# Connectors.net
KiCad netlist of a schematic drawn in Altium Designer
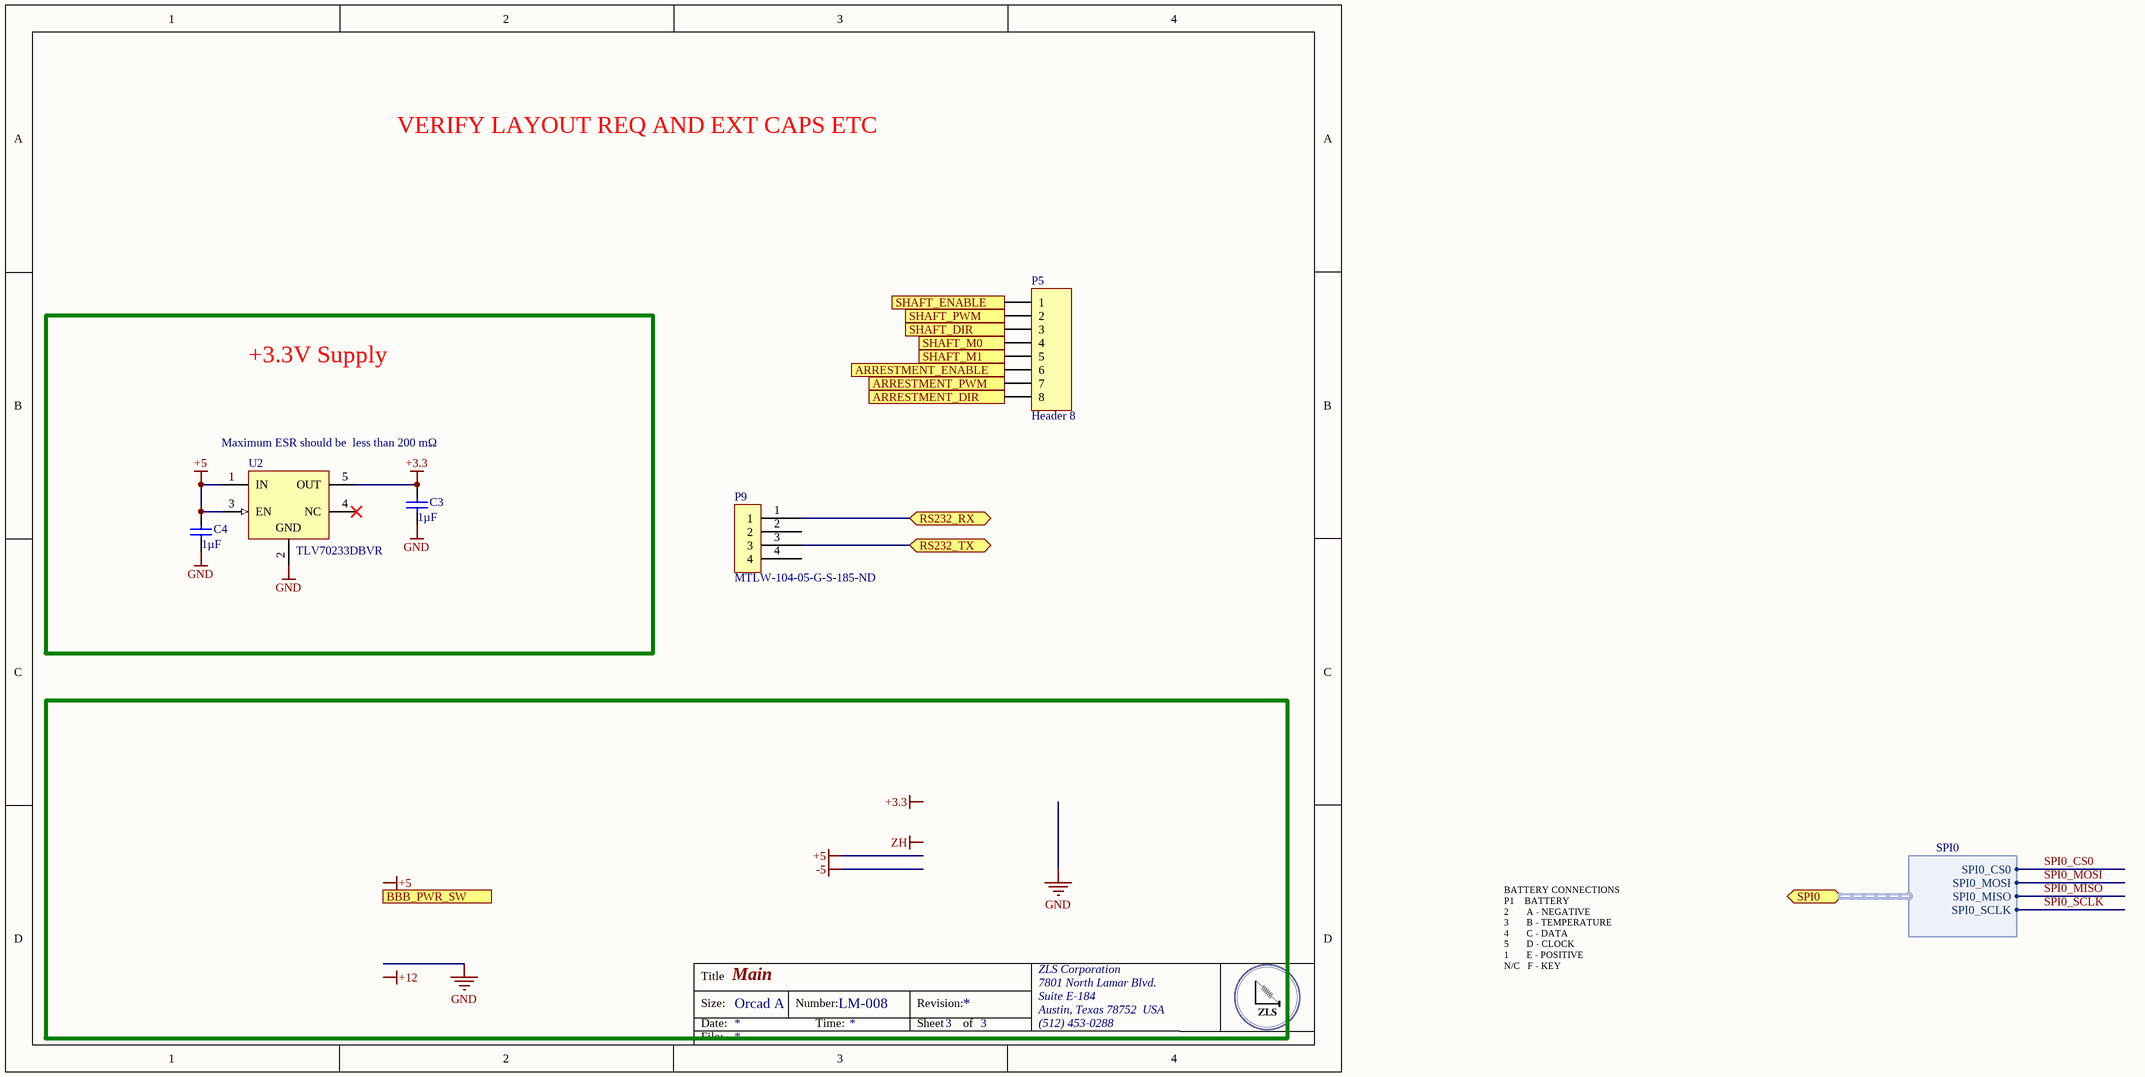
[diagram p0: Connectors.SchDoc]

(export (version "E")
  (design (tool "Eeschema 10.0.6"))
  (components
    (comp (ref "C3")
      (value "CAP CER 1UF 50V X7R 1210")
      (footprint "CAPC1206(3216)130_N")
      (fields
        (field (name "MANUFACTURER") "Murata Electronics North America")
        (field (name "MANUFACTURER PART NUMBER") "GRM32RR71H105KA01L")
        (field (name "CAPACITANCE") "1µF")
        (field (name "TOLERANCE") "±10%")
      )
      (libsource (lib "Altium Content Vault") (part "CMP-1037-04913-1"))
    )
    (comp (ref "C4")
      (value "CAP CER 1UF 50V X7R 1210")
      (footprint "CAPC1206(3216)130_N")
      (fields
        (field (name "MANUFACTURER") "Murata Electronics North America")
        (field (name "MANUFACTURER PART NUMBER") "GRM32RR71H105KA01L")
        (field (name "CAPACITANCE") "1µF")
        (field (name "TOLERANCE") "±10%")
      )
      (libsource (lib "Altium Content Vault") (part "CMP-1037-04913-1"))
    )
    (comp (ref "P5")
      (value "Header 8")
      (footprint "HDR1X8")
      (description "Header, 8-Pin")
      (fields (field (name "PUBLISHER") "Altium Limited"))
      (libsource (lib "Miscellaneous Connectors") (part "Header 8"))
    )
    (comp (ref "P9")
      (value "TLW-104-05-G-S")
      (footprint "TLW-104-05-G-S")
      (fields (field (name "SUPPLIER PART NUMBER 1") "MTLW-104-05-G-S-185-ND"))
      (libsource (lib "ZLS_Schematic_lib") (part "TLW-104-05-G-S"))
    )
    (comp (ref "U2")
      (value "TLV70233DBVR")
      (footprint "DBV0005A_N")
      (fields (field (name "MANUFACTURER") "Texas Instruments"))
      (libsource (lib "Altium Content Vault") (part "TI-TXX7XXXX-5"))
    )
  )
  (nets
    (net (code "2") (name "+3.3") (class "Default")
      (node (ref "C3") (pin "2") (pinfunction "2_2") (pintype "passive"))
      (node (ref "U2") (pin "5") (pinfunction "OUT_5") (pintype "power_in"))
    )
    (net (code "3") (name "+5") (class "Default")
      (node (ref "C4") (pin "2") (pinfunction "2_2") (pintype "passive"))
      (node (ref "U2") (pin "1") (pinfunction "IN_1") (pintype "power_in"))
      (node (ref "U2") (pin "3") (pinfunction "EN_3") (pintype "input"))
    )
    (net (code "6") (name "/ARRESTMENT_DIR") (class "Default")
      (node (ref "P5") (pin "8") (pinfunction "8_8") (pintype "passive"))
    )
    (net (code "7") (name "/ARRESTMENT_ENABLE") (class "Default")
      (node (ref "P5") (pin "6") (pinfunction "6_6") (pintype "passive"))
    )
    (net (code "8") (name "/ARRESTMENT_PWM") (class "Default")
      (node (ref "P5") (pin "7") (pinfunction "7_7") (pintype "passive"))
    )
    (net (code "10") (name "/RS232_RX") (class "Default")
      (node (ref "P9") (pin "1") (pinfunction "1_1") (pintype "passive"))
    )
    (net (code "11") (name "/RS232_TX") (class "Default")
      (node (ref "P9") (pin "3") (pinfunction "3_3") (pintype "passive"))
    )
    (net (code "12") (name "/SHAFT_DIR") (class "Default")
      (node (ref "P5") (pin "3") (pinfunction "3_3") (pintype "passive"))
    )
    (net (code "13") (name "/SHAFT_ENABLE") (class "Default")
      (node (ref "P5") (pin "1") (pinfunction "1_1") (pintype "passive"))
    )
    (net (code "14") (name "/SHAFT_M0") (class "Default")
      (node (ref "P5") (pin "4") (pinfunction "4_4") (pintype "passive"))
    )
    (net (code "15") (name "/SHAFT_M1") (class "Default")
      (node (ref "P5") (pin "5") (pinfunction "5_5") (pintype "passive"))
    )
    (net (code "16") (name "/SHAFT_PWM") (class "Default")
      (node (ref "P5") (pin "2") (pinfunction "2_2") (pintype "passive"))
    )
    (net (code "22") (name "GND") (class "Default")
      (node (ref "C3") (pin "1") (pinfunction "1_1") (pintype "passive"))
      (node (ref "C4") (pin "1") (pinfunction "1_1") (pintype "passive"))
      (node (ref "U2") (pin "2") (pinfunction "GND_2") (pintype "power_in"))
    )
    (net (code "24") (name "unconnected-(P9-Pad2)") (class "Default")
      (node (ref "P9") (pin "2") (pinfunction "2_2") (pintype "passive"))
    )
    (net (code "25") (name "unconnected-(P9-Pad4)") (class "Default")
      (node (ref "P9") (pin "4") (pinfunction "4_4") (pintype "passive"))
    )
    (net (code "26") (name "unconnected-(U2-NC-Pad4)") (class "Default")
      (node (ref "U2") (pin "4") (pinfunction "NC_4") (pintype "passive+no_connect"))
    )
  )
)
